# HF-Lipomon-pcb1.net
KiCad netlist of a schematic drawn in Altium Designer
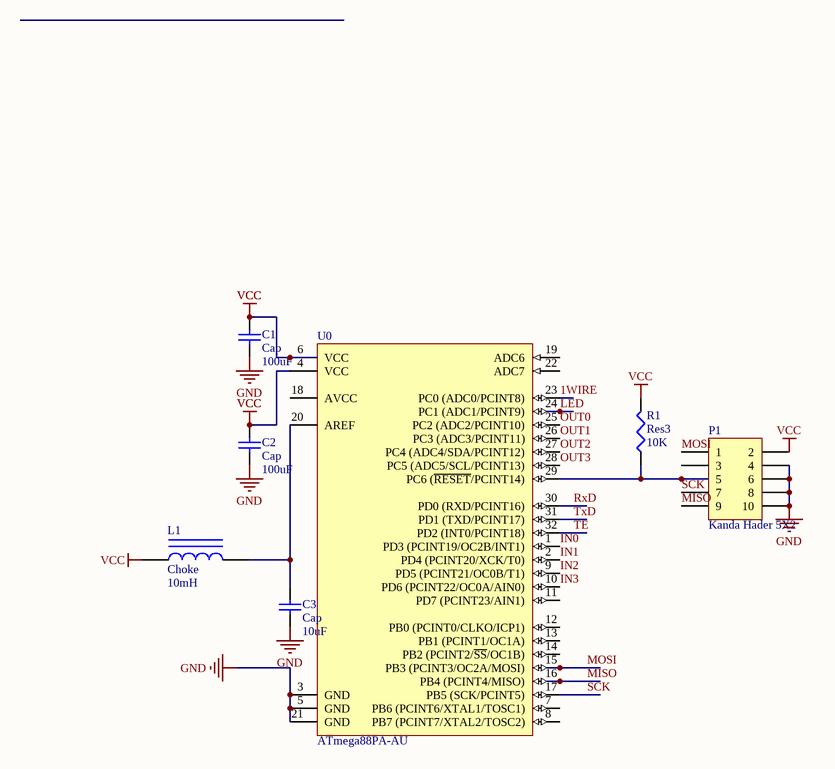
[diagram p0: HF-Lipomon-pcb1.SchDoc]

(export (version "E")
  (design (tool "Eeschema 10.0.6"))
  (components
    (comp (ref "C1")
      (value "Cap")
      (footprint "RAD-0.3")
      (description "Capacitor")
      (fields (field (name "ALTIUM_VALUE") "100uF") (field (name "PUBLISHER") "Altium Limited"))
      (libsource (lib "Miscellaneous Devices") (part "Cap"))
    )
    (comp (ref "C2")
      (value "Cap")
      (footprint "RAD-0.3")
      (description "Capacitor")
      (fields (field (name "ALTIUM_VALUE") "100uF") (field (name "PUBLISHER") "Altium Limited"))
      (libsource (lib "Miscellaneous Devices") (part "Cap"))
    )
    (comp (ref "C3")
      (value "Cap")
      (footprint "RAD-0.3")
      (description "Capacitor")
      (fields (field (name "ALTIUM_VALUE") "10uF") (field (name "PUBLISHER") "Altium Limited"))
      (libsource (lib "Miscellaneous Devices") (part "Cap"))
    )
    (comp (ref "L1")
      (value "Choke")
      (footprint "AXIAL-0.9")
      (description "Magnetic-Core Inductor")
      (fields (field (name "ALTIUM_VALUE") "10mH") (field (name "PUBLISHER") "Altium Limited"))
      (libsource (lib "Miscellaneous Devices") (part "Inductor Iron"))
    )
    (comp (ref "P1")
      (value "Kanda Hader 5X2")
      (footprint "HDR2X5")
      (description "Header, 5-Pin, Dual row")
      (fields (field (name "PUBLISHER") "Altium Limited"))
      (libsource (lib "Miscellaneous Connectors") (part "Header 5X2"))
    )
    (comp (ref "R1")
      (value "Res3")
      (footprint "6-0805_N")
      (description "Resistor")
      (fields (field (name "ALTIUM_VALUE") "10K") (field (name "PUBLISHER") "Altium Limited"))
      (libsource (lib "Miscellaneous Devices") (part "Res3"))
    )
    (comp (ref "U0")
      (value "ATmega88PA-AU")
      (footprint "32A_N")
      (fields (field (name "PUBLISHER") "Altium Limited"))
      (libsource (lib "Atmel Microcontroller 8-Bit megaAVR") (part "ATmega88PA-AU"))
    )
  )
  (nets
    (net (code "1") (name "/1WIRE") (class "Default")
      (node (ref "U0") (pin "23") (pinfunction "PC0_(ADC0/PCINT8)_23") (pintype "bidirectional"))
    )
    (net (code "2") (name "/IN0") (class "Default")
      (node (ref "U0") (pin "1") (pinfunction "PD3_(PCINT19/OC2B/INT1)_1") (pintype "bidirectional"))
    )
    (net (code "3") (name "/IN1") (class "Default")
      (node (ref "U0") (pin "2") (pinfunction "PD4_(PCINT20/XCK/T0)_2") (pintype "bidirectional"))
    )
    (net (code "4") (name "/IN2") (class "Default")
      (node (ref "U0") (pin "9") (pinfunction "PD5_(PCINT21/OC0B/T1)_9") (pintype "bidirectional"))
    )
    (net (code "5") (name "/IN3") (class "Default")
      (node (ref "U0") (pin "10") (pinfunction "PD6_(PCINT22/OC0A/AIN0)_10") (pintype "bidirectional"))
    )
    (net (code "6") (name "/LED") (class "Default")
      (node (ref "U0") (pin "24") (pinfunction "PC1_(ADC1/PCINT9)_24") (pintype "bidirectional"))
    )
    (net (code "7") (name "/MISO") (class "Default")
      (node (ref "P1") (pin "9") (pinfunction "9_9") (pintype "passive"))
      (node (ref "U0") (pin "16") (pinfunction "PB4_(PCINT4/MISO)_16") (pintype "bidirectional"))
    )
    (net (code "8") (name "/MOSI") (class "Default")
      (node (ref "P1") (pin "1") (pinfunction "1_1") (pintype "passive"))
      (node (ref "U0") (pin "15") (pinfunction "PB3_(PCINT3/OC2A/MOSI)_15") (pintype "bidirectional"))
    )
    (net (code "9") (name "/OUT0") (class "Default")
      (node (ref "U0") (pin "25") (pinfunction "PC2_(ADC2/PCINT10)_25") (pintype "bidirectional"))
    )
    (net (code "10") (name "/OUT1") (class "Default")
      (node (ref "U0") (pin "26") (pinfunction "PC3_(ADC3/PCINT11)_26") (pintype "bidirectional"))
    )
    (net (code "11") (name "/OUT2") (class "Default")
      (node (ref "U0") (pin "27") (pinfunction "PC4_(ADC4/SDA/PCINT12)_27") (pintype "bidirectional"))
    )
    (net (code "12") (name "/OUT3") (class "Default")
      (node (ref "U0") (pin "28") (pinfunction "PC5_(ADC5/SCL/PCINT13)_28") (pintype "bidirectional"))
    )
    (net (code "13") (name "/RxD") (class "Default")
      (node (ref "U0") (pin "30") (pinfunction "PD0_(RXD/PCINT16)_30") (pintype "bidirectional"))
    )
    (net (code "14") (name "/SCK") (class "Default")
      (node (ref "P1") (pin "7") (pinfunction "7_7") (pintype "passive"))
      (node (ref "U0") (pin "17") (pinfunction "PB5_(SCK/PCINT5)_17") (pintype "bidirectional"))
    )
    (net (code "15") (name "/TE") (class "Default")
      (node (ref "U0") (pin "32") (pinfunction "PD2_(INT0/PCINT18)_32") (pintype "bidirectional"))
    )
    (net (code "16") (name "/TxD") (class "Default")
      (node (ref "U0") (pin "31") (pinfunction "PD1_(TXD/PCINT17)_31") (pintype "bidirectional"))
    )
    (net (code "17") (name "GND") (class "Default")
      (node (ref "C1") (pin "1") (pinfunction "1_1") (pintype "passive"))
      (node (ref "C2") (pin "1") (pinfunction "1_1") (pintype "passive"))
      (node (ref "C3") (pin "1") (pinfunction "1_1") (pintype "passive"))
      (node (ref "P1") (pin "10") (pinfunction "10_10") (pintype "passive"))
      (node (ref "P1") (pin "4") (pinfunction "4_4") (pintype "passive"))
      (node (ref "P1") (pin "6") (pinfunction "6_6") (pintype "passive"))
      (node (ref "P1") (pin "8") (pinfunction "8_8") (pintype "passive"))
      (node (ref "U0") (pin "21") (pinfunction "GND_21") (pintype "power_in"))
      (node (ref "U0") (pin "3") (pinfunction "GND_3") (pintype "power_in"))
      (node (ref "U0") (pin "5") (pinfunction "GND_5") (pintype "power_in"))
    )
    (net (code "18") (name "Net-(U0-AREF)") (class "Default")
      (node (ref "C3") (pin "2") (pinfunction "2_2") (pintype "passive"))
      (node (ref "L1") (pin "2") (pinfunction "2_2") (pintype "passive"))
      (node (ref "U0") (pin "20") (pinfunction "AREF_20") (pintype "passive"))
    )
    (net (code "19") (name "Net-(U0-PC6_(~{RESET}{slash}PCINT14))") (class "Default")
      (node (ref "P1") (pin "5") (pinfunction "5_5") (pintype "passive"))
      (node (ref "R1") (pin "1") (pinfunction "1_1") (pintype "passive"))
      (node (ref "U0") (pin "29") (pinfunction "PC6_(~{RESET}/PCINT14)_29") (pintype "bidirectional"))
    )
    (net (code "20") (name "VCC") (class "Default")
      (node (ref "C1") (pin "2") (pinfunction "2_2") (pintype "passive"))
      (node (ref "C2") (pin "2") (pinfunction "2_2") (pintype "passive"))
      (node (ref "L1") (pin "1") (pinfunction "1_1") (pintype "passive"))
      (node (ref "P1") (pin "2") (pinfunction "2_2") (pintype "passive"))
      (node (ref "R1") (pin "2") (pinfunction "2_2") (pintype "passive"))
      (node (ref "U0") (pin "4") (pinfunction "VCC_4") (pintype "power_in"))
      (node (ref "U0") (pin "6") (pinfunction "VCC_6") (pintype "power_in"))
    )
    (net (code "21") (name "unconnected-(P1-Pad3)") (class "Default")
      (node (ref "P1") (pin "3") (pinfunction "3_3") (pintype "passive"))
    )
    (net (code "22") (name "unconnected-(U0-ADC6-Pad19)") (class "Default")
      (node (ref "U0") (pin "19") (pinfunction "ADC6_19") (pintype "input"))
    )
    (net (code "23") (name "unconnected-(U0-ADC7-Pad22)") (class "Default")
      (node (ref "U0") (pin "22") (pinfunction "ADC7_22") (pintype "input"))
    )
    (net (code "24") (name "unconnected-(U0-AVCC-Pad18)") (class "Default")
      (node (ref "U0") (pin "18") (pinfunction "AVCC_18") (pintype "power_in"))
    )
    (net (code "25") (name "unconnected-(U0-PB0_(PCINT0{slash}CLKO{slash}ICP1)-Pad12)") (class "Default")
      (node (ref "U0") (pin "12") (pinfunction "PB0_(PCINT0/CLKO/ICP1)_12") (pintype "bidirectional"))
    )
    (net (code "26") (name "unconnected-(U0-PB1_(PCINT1{slash}OC1A)-Pad13)") (class "Default")
      (node (ref "U0") (pin "13") (pinfunction "PB1_(PCINT1/OC1A)_13") (pintype "bidirectional"))
    )
    (net (code "27") (name "unconnected-(U0-PB2_(PCINT2{slash}~{SS}{slash}OC1B)-Pad14)") (class "Default")
      (node (ref "U0") (pin "14") (pinfunction "PB2_(PCINT2/~{SS}/OC1B)_14") (pintype "bidirectional"))
    )
    (net (code "28") (name "unconnected-(U0-PB6_(PCINT6{slash}XTAL1{slash}TOSC1)-Pad7)") (class "Default")
      (node (ref "U0") (pin "7") (pinfunction "PB6_(PCINT6/XTAL1/TOSC1)_7") (pintype "bidirectional"))
    )
    (net (code "29") (name "unconnected-(U0-PB7_(PCINT7{slash}XTAL2{slash}TOSC2)-Pad8)") (class "Default")
      (node (ref "U0") (pin "8") (pinfunction "PB7_(PCINT7/XTAL2/TOSC2)_8") (pintype "bidirectional"))
    )
    (net (code "30") (name "unconnected-(U0-PD7_(PCINT23{slash}AIN1)-Pad11)") (class "Default")
      (node (ref "U0") (pin "11") (pinfunction "PD7_(PCINT23/AIN1)_11") (pintype "bidirectional"))
    )
  )
)
